# Boost_Converter_Circuit.net
KiCad netlist of a schematic drawn in EAGLE
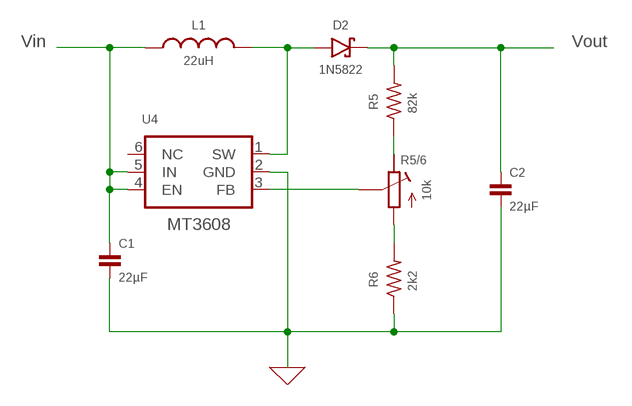
[diagram p0: schematic, sheet 1]

(export (version "E")
  (design (tool "Eeschema 10.0.6"))
  (components
    (comp (ref "C1")
      (value "22µF")
      (footprint "eagle-import:C1206")
      (libsource (lib "eagle-import") (part "CAPACITOR-1206"))
    )
    (comp (ref "C2")
      (value "22µF")
      (footprint "eagle-import:C1206")
      (libsource (lib "eagle-import") (part "CAPACITOR-1206"))
    )
    (comp (ref "D2")
      (value "1N5822")
      (footprint "eagle-import:DIODE_SMB")
      (libsource (lib "eagle-import") (part "DIODE-SCHOTTKY-1N5822"))
    )
    (comp (ref "L1")
      (value "22uH")
      (footprint "eagle-import:CDRH104R+6D28")
      (libsource (lib "eagle-import") (part "INDUCTOR-CDRH104R/6D28L5038P"))
    )
    (comp (ref "R5")
      (value "82k")
      (footprint "eagle-import:R0805")
      (libsource (lib "eagle-import") (part "RESISTORR0805"))
    )
    (comp (ref "R5/6")
      (value "10k")
      (footprint "eagle-import:RTRIM64P")
      (libsource (lib "eagle-import") (part "RESISTOR-TRIMM-BAOTER-HORIZONTAL"))
    )
    (comp (ref "R6")
      (value "2k2")
      (footprint "eagle-import:R0805")
      (libsource (lib "eagle-import") (part "RESISTORR0805"))
    )
    (comp (ref "U4")
      (value "MT3608")
      (footprint "eagle-import:SOT-23-6")
      (libsource (lib "eagle-import") (part "MT3608"))
    )
  )
  (nets
    (net (code "1") (name "GND") (class "Default")
      (node (ref "C1") (pin "2") (pinfunction "2_2") (pintype "passive"))
      (node (ref "C2") (pin "2") (pinfunction "2_2") (pintype "passive"))
      (node (ref "R6") (pin "1") (pinfunction "1_1") (pintype "passive"))
      (node (ref "U4") (pin "2") (pinfunction "GND_2") (pintype "power_in"))
    )
    (net (code "2") (name "Net-(C2-Pad1)") (class "Default")
      (node (ref "C2") (pin "1") (pinfunction "1_1") (pintype "passive"))
      (node (ref "D2") (pin "C") (pinfunction "C_C") (pintype "passive"))
      (node (ref "R5") (pin "2") (pinfunction "2_2") (pintype "passive"))
    )
    (net (code "3") (name "Net-(R5/6-A)") (class "Default")
      (node (ref "R5/6") (pin "1") (pinfunction "A_1") (pintype "passive"))
      (node (ref "R6") (pin "2") (pinfunction "2_2") (pintype "passive"))
    )
    (net (code "4") (name "Net-(R5/6-E)") (class "Default")
      (node (ref "R5") (pin "1") (pinfunction "1_1") (pintype "passive"))
      (node (ref "R5/6") (pin "3") (pinfunction "E_3") (pintype "passive"))
    )
    (net (code "5") (name "Net-(R5/6-S)") (class "Default")
      (node (ref "R5/6") (pin "2") (pinfunction "S_2") (pintype "passive"))
      (node (ref "U4") (pin "3") (pinfunction "FB_3") (pintype "input"))
    )
    (net (code "6") (name "Net-(U4-EN)") (class "Default")
      (node (ref "C1") (pin "1") (pinfunction "1_1") (pintype "passive"))
      (node (ref "L1") (pin "2") (pinfunction "2_2") (pintype "passive"))
      (node (ref "U4") (pin "4") (pinfunction "EN_4") (pintype "input"))
      (node (ref "U4") (pin "5") (pinfunction "IN_5") (pintype "power_in"))
    )
    (net (code "7") (name "Net-(U4-SW)") (class "Default")
      (node (ref "D2") (pin "A") (pinfunction "A_A") (pintype "passive"))
      (node (ref "L1") (pin "1") (pinfunction "1_1") (pintype "passive"))
      (node (ref "U4") (pin "1") (pinfunction "SW_1") (pintype "power_in"))
    )
    (net (code "8") (name "unconnected-(U4-NC-Pad6)") (class "Default")
      (node (ref "U4") (pin "6") (pinfunction "NC_6") (pintype "no_connect"))
    )
  )
)
